# Y-babies_ATtiny84_v02.net
KiCad netlist of a schematic drawn in EAGLE
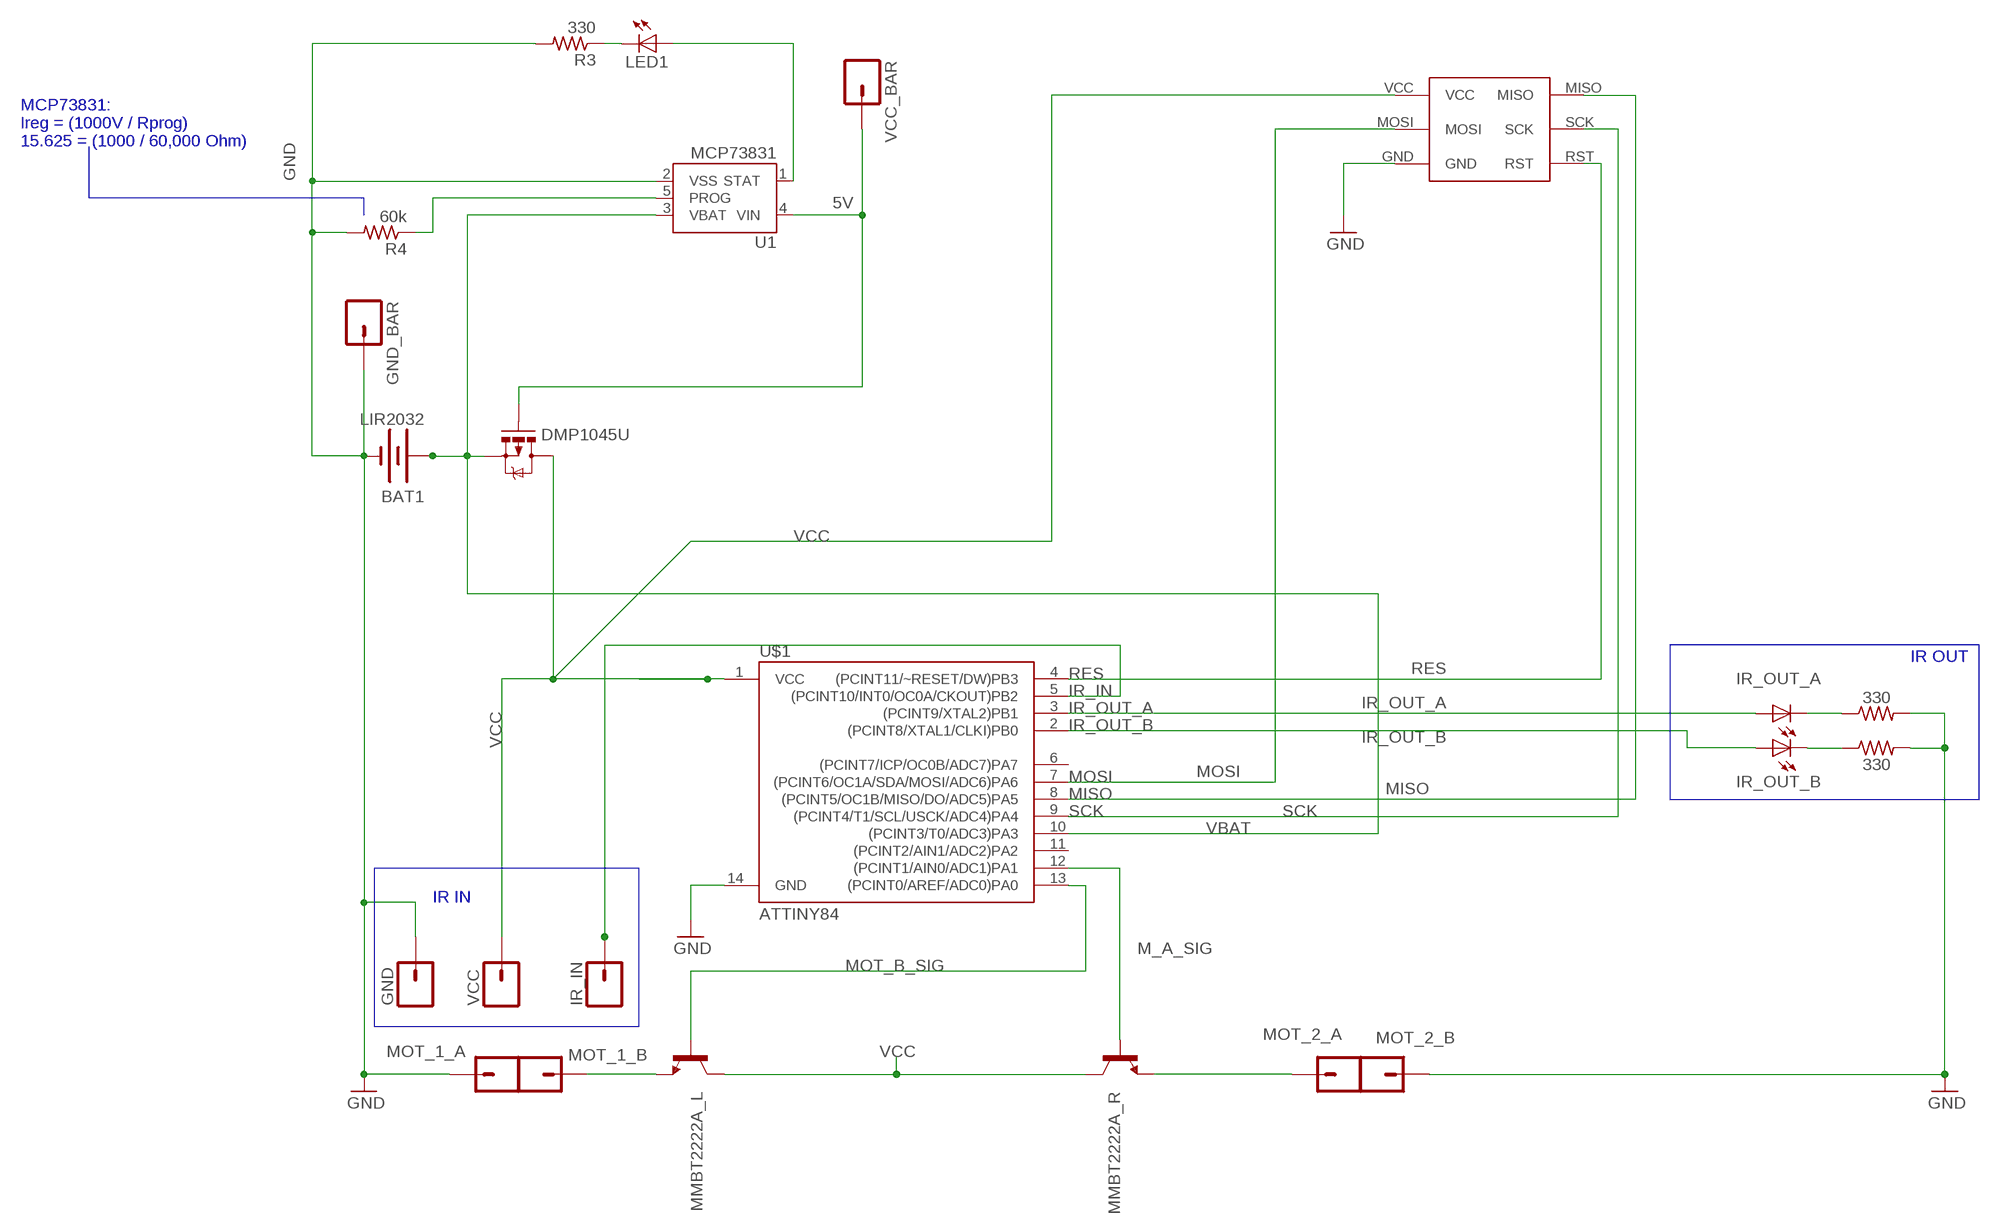
[diagram p0: schematic, sheet 1]

(export (version "E")
  (design (tool "Eeschema 10.0.6"))
  (components
    (comp (ref "BAT1")
      (value "LIR2032")
      (footprint "eagle-import:BATTCOM_20MM_PTH")
      (libsource (lib "eagle-import") (part "BATTERY20PTH"))
    )
    (comp (ref "DMP1045U")
      (value "MOSFET-PCHANNELSMD")
      (footprint "eagle-import:SOT23-3")
      (libsource (lib "eagle-import") (part "MOSFET-PCHANNELSMD"))
    )
    (comp (ref "GND")
      (value "M01PTH")
      (footprint "eagle-import:1X01")
      (libsource (lib "eagle-import") (part "M01PTH"))
    )
    (comp (ref "GND_BAR")
      (value "M01PTH")
      (footprint "eagle-import:1X01")
      (libsource (lib "eagle-import") (part "M01PTH"))
    )
    (comp (ref "IR_IN")
      (value "M01PTH")
      (footprint "eagle-import:1X01")
      (libsource (lib "eagle-import") (part "M01PTH"))
    )
    (comp (ref "IR_OUT_A")
      (value "LED3MM")
      (footprint "eagle-import:LED3MM")
      (libsource (lib "eagle-import") (part "LED3MM"))
    )
    (comp (ref "IR_OUT_B")
      (value "LED3MM")
      (footprint "eagle-import:LED3MM")
      (libsource (lib "eagle-import") (part "LED3MM"))
    )
    (comp (ref "LED1")
      (value "LEDSML0603")
      (footprint "eagle-import:SML0603")
      (libsource (lib "eagle-import") (part "LEDSML0603"))
    )
    (comp (ref "MMBT2222A_L")
      (value "TRANSISTOR_NPNSOT23")
      (footprint "eagle-import:SOT23")
      (libsource (lib "eagle-import") (part "TRANSISTOR_NPNSOT23"))
    )
    (comp (ref "MMBT2222A_R")
      (value "TRANSISTOR_NPNSOT23")
      (footprint "eagle-import:SOT23")
      (libsource (lib "eagle-import") (part "TRANSISTOR_NPNSOT23"))
    )
    (comp (ref "MOT_1_A")
      (value "M01SMD-4.5X1.5")
      (footprint "eagle-import:PAD-1.5X4.5")
      (libsource (lib "eagle-import") (part "M01SMD-4.5X1.5"))
    )
    (comp (ref "MOT_1_B")
      (value "M01SMD-4.5X1.5")
      (footprint "eagle-import:PAD-1.5X4.5")
      (libsource (lib "eagle-import") (part "M01SMD-4.5X1.5"))
    )
    (comp (ref "MOT_2_A")
      (value "M01SMD-4.5X1.5")
      (footprint "eagle-import:PAD-1.5X4.5")
      (libsource (lib "eagle-import") (part "M01SMD-4.5X1.5"))
    )
    (comp (ref "MOT_2_B")
      (value "M01SMD-4.5X1.5")
      (footprint "eagle-import:PAD-1.5X4.5")
      (libsource (lib "eagle-import") (part "M01SMD-4.5X1.5"))
    )
    (comp (ref "R1")
      (value "330")
      (footprint "eagle-import:R0402")
      (libsource (lib "eagle-import") (part "R-US_R0402"))
    )
    (comp (ref "R2")
      (value "330")
      (footprint "eagle-import:R0402")
      (libsource (lib "eagle-import") (part "R-US_R0402"))
    )
    (comp (ref "R3")
      (value "330")
      (footprint "eagle-import:R0402")
      (libsource (lib "eagle-import") (part "R-US_R0402"))
    )
    (comp (ref "R4")
      (value "60k")
      (footprint "eagle-import:R0402")
      (libsource (lib "eagle-import") (part "R-US_R0402"))
    )
    (comp (ref "U$1")
      (value "ATTINY84")
      (footprint "eagle-import:SO14")
      (libsource (lib "eagle-import") (part "ATTINY84"))
    )
    (comp (ref "U$2")
      (value "POGO_PIN_SPI_PAD")
      (footprint "eagle-import:POGO_PIN_SPI_PAD")
      (libsource (lib "eagle-import") (part "POGO_PIN_SPI_PAD"))
    )
    (comp (ref "U1")
      (value "MCP73831")
      (footprint "eagle-import:SOT23-5")
      (libsource (lib "eagle-import") (part "MCP73831"))
    )
    (comp (ref "VCC")
      (value "M01PTH")
      (footprint "eagle-import:1X01")
      (libsource (lib "eagle-import") (part "M01PTH"))
    )
    (comp (ref "VCC_BAR")
      (value "M01PTH")
      (footprint "eagle-import:1X01")
      (libsource (lib "eagle-import") (part "M01PTH"))
    )
  )
  (nets
    (net (code "1") (name "/5V") (class "Default")
      (node (ref "DMP1045U") (pin "1") (pinfunction "G_1") (pintype "passive"))
      (node (ref "U1") (pin "4") (pinfunction "VIN_4") (pintype "power_in"))
      (node (ref "VCC_BAR") (pin "1") (pinfunction "1_1") (pintype "passive"))
    )
    (net (code "2") (name "/IR_IN") (class "Default")
      (node (ref "IR_IN") (pin "1") (pinfunction "1_1") (pintype "passive"))
      (node (ref "U$1") (pin "5") (pinfunction "(PCINT10/INT0/OC0A/CKOUT)PB2_5") (pintype "bidirectional"))
    )
    (net (code "3") (name "/IR_OUT_A") (class "Default")
      (node (ref "IR_OUT_A") (pin "A") (pinfunction "A_A") (pintype "passive"))
      (node (ref "U$1") (pin "3") (pinfunction "(PCINT9/XTAL2)PB1_3") (pintype "bidirectional"))
    )
    (net (code "4") (name "/IR_OUT_B") (class "Default")
      (node (ref "IR_OUT_B") (pin "A") (pinfunction "A_A") (pintype "passive"))
      (node (ref "U$1") (pin "2") (pinfunction "(PCINT8/XTAL1/CLKI)PB0_2") (pintype "bidirectional"))
    )
    (net (code "5") (name "/MISO") (class "Default")
      (node (ref "U$1") (pin "8") (pinfunction "(PCINT5/OC1B/MISO/DO/ADC5)PA5_8") (pintype "bidirectional"))
      (node (ref "U$2") (pin "MISO") (pinfunction "MISO_MISO") (pintype "bidirectional"))
    )
    (net (code "6") (name "/MOSI") (class "Default")
      (node (ref "U$1") (pin "7") (pinfunction "(PCINT6/OC1A/SDA/MOSI/ADC6)PA6_7") (pintype "bidirectional"))
      (node (ref "U$2") (pin "MOSI") (pinfunction "MOSI_MOSI") (pintype "bidirectional"))
    )
    (net (code "7") (name "/MOT_B_SIG") (class "Default")
      (node (ref "MMBT2222A_L") (pin "1") (pinfunction "B_1") (pintype "passive"))
      (node (ref "U$1") (pin "13") (pinfunction "(PCINT0/AREF/ADC0)PA0_13") (pintype "bidirectional"))
    )
    (net (code "8") (name "/M_A_SIG") (class "Default")
      (node (ref "MMBT2222A_R") (pin "1") (pinfunction "B_1") (pintype "passive"))
      (node (ref "U$1") (pin "12") (pinfunction "(PCINT1/AIN0/ADC1)PA1_12") (pintype "bidirectional"))
    )
    (net (code "9") (name "/RES") (class "Default")
      (node (ref "U$1") (pin "4") (pinfunction "(PCINT11/~{RESET/DW})PB3_4") (pintype "bidirectional"))
      (node (ref "U$2") (pin "RST") (pinfunction "RST_RST") (pintype "bidirectional"))
    )
    (net (code "10") (name "/SCK") (class "Default")
      (node (ref "U$1") (pin "9") (pinfunction "(PCINT4/T1/SCL/USCK/ADC4)PA4_9") (pintype "bidirectional"))
      (node (ref "U$2") (pin "SCK") (pinfunction "SCK_SCK") (pintype "bidirectional"))
    )
    (net (code "11") (name "/VBAT") (class "Default")
      (node (ref "BAT1") (pin "1") (pinfunction "+_1") (pintype "power_in"))
      (node (ref "DMP1045U") (pin "2") (pinfunction "S_2") (pintype "passive"))
      (node (ref "U$1") (pin "10") (pinfunction "(PCINT3/T0/ADC3)PA3_10") (pintype "bidirectional"))
      (node (ref "U1") (pin "3") (pinfunction "VBAT_3") (pintype "power_in"))
    )
    (net (code "12") (name "/VCC") (class "Default")
      (node (ref "DMP1045U") (pin "3") (pinfunction "D_3") (pintype "passive"))
      (node (ref "MMBT2222A_L") (pin "3") (pinfunction "C_3") (pintype "passive"))
      (node (ref "MMBT2222A_R") (pin "3") (pinfunction "C_3") (pintype "passive"))
      (node (ref "U$1") (pin "1") (pinfunction "VCC_1") (pintype "bidirectional"))
      (node (ref "U$2") (pin "VCC") (pinfunction "VCC_VCC") (pintype "bidirectional"))
      (node (ref "VCC") (pin "1") (pinfunction "1_1") (pintype "passive"))
    )
    (net (code "13") (name "GND") (class "Default")
      (node (ref "BAT1") (pin "2") (pinfunction "-_2") (pintype "power_in"))
      (node (ref "GND") (pin "1") (pinfunction "1_1") (pintype "passive"))
      (node (ref "GND_BAR") (pin "1") (pinfunction "1_1") (pintype "passive"))
      (node (ref "MOT_1_A") (pin "P$1") (pinfunction "1_P$1") (pintype "passive"))
      (node (ref "MOT_2_B") (pin "P$1") (pinfunction "1_P$1") (pintype "passive"))
      (node (ref "R1") (pin "2") (pinfunction "2_2") (pintype "passive"))
      (node (ref "R2") (pin "2") (pinfunction "2_2") (pintype "passive"))
      (node (ref "R3") (pin "2") (pinfunction "2_2") (pintype "passive"))
      (node (ref "R4") (pin "2") (pinfunction "2_2") (pintype "passive"))
      (node (ref "U$1") (pin "14") (pinfunction "GND_14") (pintype "bidirectional"))
      (node (ref "U$2") (pin "GND") (pinfunction "GND_GND") (pintype "bidirectional"))
      (node (ref "U1") (pin "2") (pinfunction "VSS_2") (pintype "power_in"))
    )
    (net (code "14") (name "Net-(IR_OUT_A-C)") (class "Default")
      (node (ref "IR_OUT_A") (pin "K") (pinfunction "C_K") (pintype "passive"))
      (node (ref "R1") (pin "1") (pinfunction "1_1") (pintype "passive"))
    )
    (net (code "15") (name "Net-(IR_OUT_B-C)") (class "Default")
      (node (ref "IR_OUT_B") (pin "K") (pinfunction "C_K") (pintype "passive"))
      (node (ref "R2") (pin "1") (pinfunction "1_1") (pintype "passive"))
    )
    (net (code "16") (name "Net-(LED1-PadC)") (class "Default")
      (node (ref "LED1") (pin "C") (pinfunction "C_C") (pintype "passive"))
      (node (ref "R3") (pin "1") (pinfunction "1_1") (pintype "passive"))
    )
    (net (code "17") (name "Net-(MMBT2222A_L-E)") (class "Default")
      (node (ref "MMBT2222A_L") (pin "2") (pinfunction "E_2") (pintype "passive"))
      (node (ref "MOT_1_B") (pin "P$1") (pinfunction "1_P$1") (pintype "passive"))
    )
    (net (code "18") (name "Net-(MMBT2222A_R-E)") (class "Default")
      (node (ref "MMBT2222A_R") (pin "2") (pinfunction "E_2") (pintype "passive"))
      (node (ref "MOT_2_A") (pin "P$1") (pinfunction "1_P$1") (pintype "passive"))
    )
    (net (code "19") (name "Net-(U1-PROG)") (class "Default")
      (node (ref "R4") (pin "1") (pinfunction "1_1") (pintype "passive"))
      (node (ref "U1") (pin "5") (pinfunction "PROG_5") (pintype "input"))
    )
    (net (code "20") (name "Net-(U1-STAT)") (class "Default")
      (node (ref "LED1") (pin "A") (pinfunction "A_A") (pintype "passive"))
      (node (ref "U1") (pin "1") (pinfunction "STAT_1") (pintype "output"))
    )
    (net (code "21") (name "unconnected-(U$1-(PCINT2{slash}AIN1{slash}ADC2)PA2-Pad11)") (class "Default")
      (node (ref "U$1") (pin "11") (pinfunction "(PCINT2/AIN1/ADC2)PA2_11") (pintype "bidirectional"))
    )
    (net (code "22") (name "unconnected-(U$1-(PCINT7{slash}ICP{slash}OC0B{slash}ADC7)PA7-Pad6)") (class "Default")
      (node (ref "U$1") (pin "6") (pinfunction "(PCINT7/ICP/OC0B/ADC7)PA7_6") (pintype "bidirectional"))
    )
  )
)
